# QCopterFC_SD_Sch.net
KiCad netlist of a schematic drawn in Altium Designer
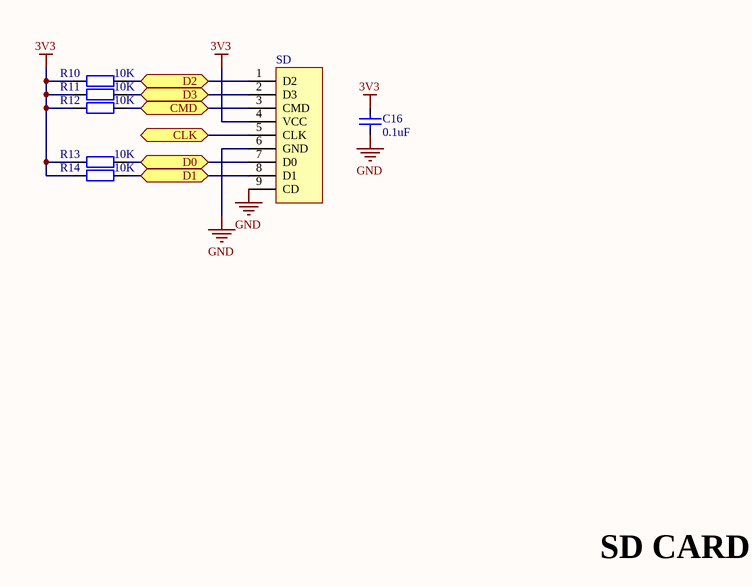
[diagram p0: QCopterFC_SD_Sch.SchDoc]

(export (version "E")
  (design (tool "Eeschema 10.0.6"))
  (components
    (comp (ref "C16")
      (value "0.1uF")
      (footprint "PCB_Passive:CAP_0603")
      (description "Capacitor")
      (fields (field (name "Comment") "Cap_0603"))
      (libsource (lib "SCH_Passive") (part "Cap_0603"))
    )
    (comp (ref "R10")
      (value "10K")
      (footprint "PCB_Passive:RES_0603")
      (description "Resistor")
      (fields (field (name "Comment") "Res_0603"))
      (libsource (lib "SCH_Passive") (part "Res_0603"))
    )
    (comp (ref "R11")
      (value "10K")
      (footprint "PCB_Passive:RES_0603")
      (description "Resistor")
      (fields (field (name "Comment") "Res_0603"))
      (libsource (lib "SCH_Passive") (part "Res_0603"))
    )
    (comp (ref "R12")
      (value "10K")
      (footprint "PCB_Passive:RES_0603")
      (description "Resistor")
      (fields (field (name "Comment") "Res_0603"))
      (libsource (lib "SCH_Passive") (part "Res_0603"))
    )
    (comp (ref "R13")
      (value "10K")
      (footprint "PCB_Passive:RES_0603")
      (description "Resistor")
      (fields (field (name "Comment") "Res_0603"))
      (libsource (lib "SCH_Passive") (part "Res_0603"))
    )
    (comp (ref "R14")
      (value "10K")
      (footprint "PCB_Passive:RES_0603")
      (description "Resistor")
      (fields (field (name "Comment") "Res_0603"))
      (libsource (lib "SCH_Passive") (part "Res_0603"))
    )
    (comp (ref "SD")
      (value "SD_Card_TF")
      (footprint "PCB_SDCard:SD_Card_TF")
      (description "SD")
      (libsource (lib "SCH_SDCard") (part "SD_Card_TF"))
    )
  )
  (nets
    (net (code "1") (name "/CLK") (class "Default")
      (node (ref "SD") (pin "5") (pinfunction "CLK_5") (pintype "passive"))
    )
    (net (code "2") (name "/CMD") (class "Default")
      (node (ref "R12") (pin "2") (pinfunction "2_2") (pintype "passive"))
      (node (ref "SD") (pin "3") (pinfunction "CMD_3") (pintype "passive"))
    )
    (net (code "3") (name "/D0") (class "Default")
      (node (ref "R13") (pin "2") (pinfunction "2_2") (pintype "passive"))
      (node (ref "SD") (pin "7") (pinfunction "D0_7") (pintype "passive"))
    )
    (net (code "4") (name "/D1") (class "Default")
      (node (ref "R14") (pin "2") (pinfunction "2_2") (pintype "passive"))
      (node (ref "SD") (pin "8") (pinfunction "D1_8") (pintype "passive"))
    )
    (net (code "5") (name "/D2") (class "Default")
      (node (ref "R10") (pin "2") (pinfunction "2_2") (pintype "passive"))
      (node (ref "SD") (pin "1") (pinfunction "D2_1") (pintype "passive"))
    )
    (net (code "6") (name "/D3") (class "Default")
      (node (ref "R11") (pin "2") (pinfunction "2_2") (pintype "passive"))
      (node (ref "SD") (pin "2") (pinfunction "D3_2") (pintype "passive"))
    )
    (net (code "8") (name "3V3") (class "Default")
      (node (ref "C16") (pin "2") (pinfunction "2_2") (pintype "passive"))
      (node (ref "R10") (pin "1") (pinfunction "1_1") (pintype "passive"))
      (node (ref "R11") (pin "1") (pinfunction "1_1") (pintype "passive"))
      (node (ref "R12") (pin "1") (pinfunction "1_1") (pintype "passive"))
      (node (ref "R13") (pin "1") (pinfunction "1_1") (pintype "passive"))
      (node (ref "R14") (pin "1") (pinfunction "1_1") (pintype "passive"))
      (node (ref "SD") (pin "4") (pinfunction "VCC_4") (pintype "passive"))
    )
    (net (code "9") (name "GND") (class "Default")
      (node (ref "C16") (pin "1") (pinfunction "1_1") (pintype "passive"))
      (node (ref "SD") (pin "6") (pinfunction "GND_6") (pintype "passive"))
      (node (ref "SD") (pin "9") (pinfunction "CD_9") (pintype "passive"))
    )
  )
)
